# pocketmdm.net
KiCad netlist of a schematic drawn in EAGLE
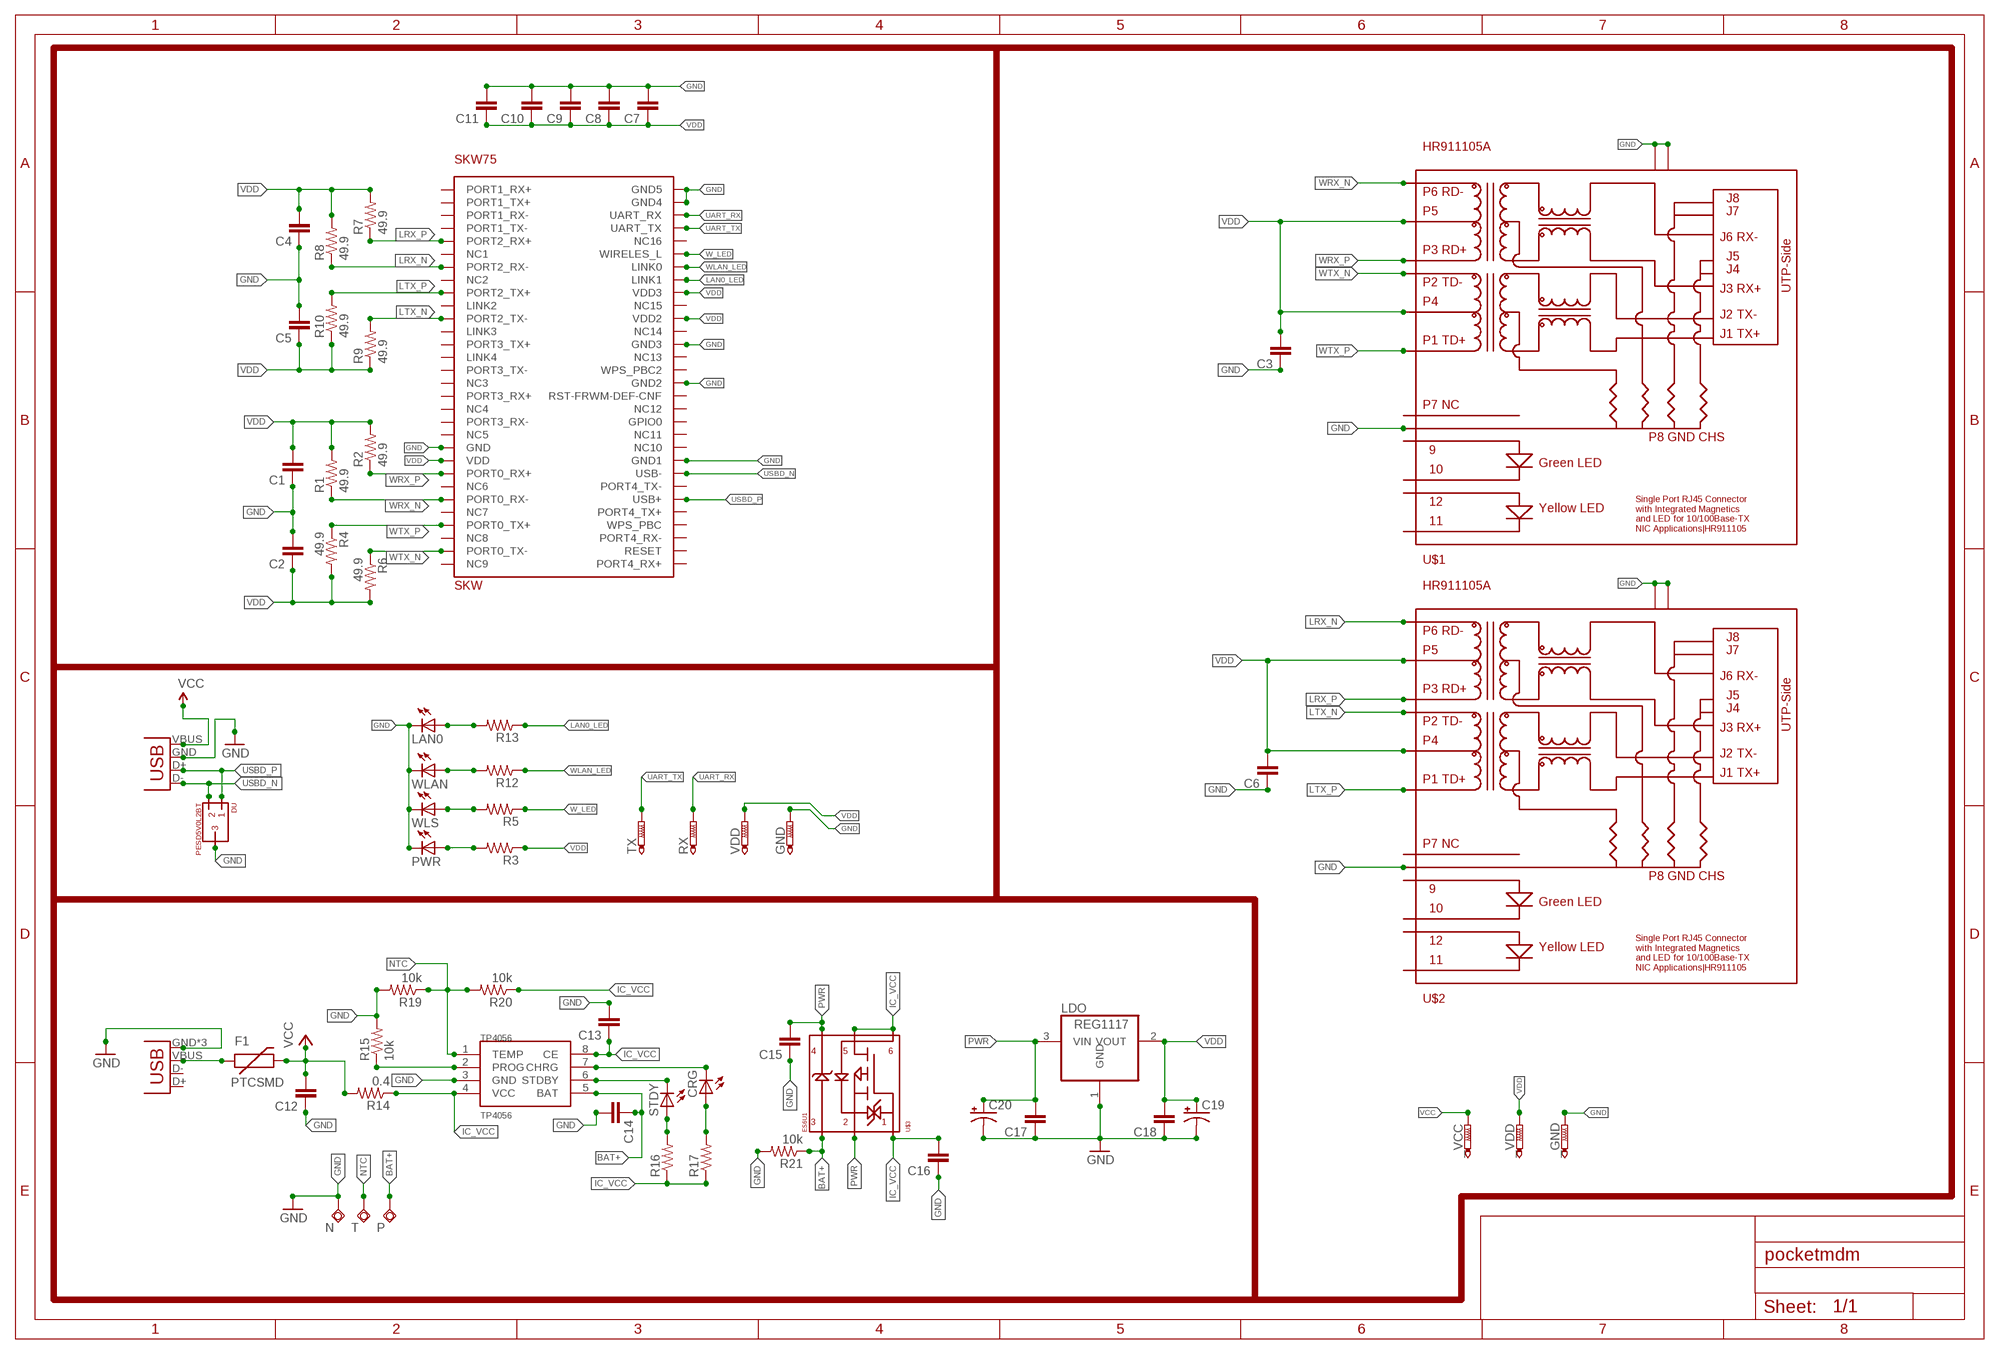
[diagram p0: schematic, sheet 1]

(export (version "E")
  (design (tool "Eeschema 10.0.6"))
  (components
    (comp (ref "C1")
      (value "CAP0402-CAP")
      (footprint "eagle-import:0402-CAP")
      (libsource (lib "eagle-import") (part "CAP0402-CAP"))
    )
    (comp (ref "C2")
      (value "CAP0402-CAP")
      (footprint "eagle-import:0402-CAP")
      (libsource (lib "eagle-import") (part "CAP0402-CAP"))
    )
    (comp (ref "C3")
      (value "CAP0402-CAP")
      (footprint "eagle-import:0402-CAP")
      (libsource (lib "eagle-import") (part "CAP0402-CAP"))
    )
    (comp (ref "C4")
      (value "CAP0402-CAP")
      (footprint "eagle-import:0402-CAP")
      (libsource (lib "eagle-import") (part "CAP0402-CAP"))
    )
    (comp (ref "C5")
      (value "CAP0402-CAP")
      (footprint "eagle-import:0402-CAP")
      (libsource (lib "eagle-import") (part "CAP0402-CAP"))
    )
    (comp (ref "C6")
      (value "CAP0402-CAP")
      (footprint "eagle-import:0402-CAP")
      (libsource (lib "eagle-import") (part "CAP0402-CAP"))
    )
    (comp (ref "C7")
      (value "CAP0402-CAP")
      (footprint "eagle-import:0402-CAP")
      (libsource (lib "eagle-import") (part "CAP0402-CAP"))
    )
    (comp (ref "C8")
      (value "CAP0402-CAP")
      (footprint "eagle-import:0402-CAP")
      (libsource (lib "eagle-import") (part "CAP0402-CAP"))
    )
    (comp (ref "C9")
      (value "CAP0402-CAP")
      (footprint "eagle-import:0402-CAP")
      (libsource (lib "eagle-import") (part "CAP0402-CAP"))
    )
    (comp (ref "C10")
      (value "CAP0402-CAP")
      (footprint "eagle-import:0402-CAP")
      (libsource (lib "eagle-import") (part "CAP0402-CAP"))
    )
    (comp (ref "C11")
      (value "CAP0402-CAP")
      (footprint "eagle-import:0402-CAP")
      (libsource (lib "eagle-import") (part "CAP0402-CAP"))
    )
    (comp (ref "C12")
      (value "CAP0402-CAP")
      (footprint "eagle-import:0402-CAP")
      (libsource (lib "eagle-import") (part "CAP0402-CAP"))
    )
    (comp (ref "C13")
      (value "CAP0402-CAP")
      (footprint "eagle-import:0402-CAP")
      (libsource (lib "eagle-import") (part "CAP0402-CAP"))
    )
    (comp (ref "C14")
      (value "CAP0402-CAP")
      (footprint "eagle-import:0402-CAP")
      (libsource (lib "eagle-import") (part "CAP0402-CAP"))
    )
    (comp (ref "C15")
      (value "CAP0402-CAP")
      (footprint "eagle-import:0402-CAP")
      (libsource (lib "eagle-import") (part "CAP0402-CAP"))
    )
    (comp (ref "C16")
      (value "CAP0402-CAP")
      (footprint "eagle-import:0402-CAP")
      (libsource (lib "eagle-import") (part "CAP0402-CAP"))
    )
    (comp (ref "C17")
      (value "CAP0402-CAP")
      (footprint "eagle-import:0402-CAP")
      (libsource (lib "eagle-import") (part "CAP0402-CAP"))
    )
    (comp (ref "C18")
      (value "CAP0402-CAP")
      (footprint "eagle-import:0402-CAP")
      (libsource (lib "eagle-import") (part "CAP0402-CAP"))
    )
    (comp (ref "C19")
      (value "CAP_POLPTH1")
      (footprint "eagle-import:CPOL-RADIAL-100UF-25V")
      (libsource (lib "eagle-import") (part "CAP_POLPTH1"))
    )
    (comp (ref "C20")
      (value "CAP_POLPTH1")
      (footprint "eagle-import:CPOL-RADIAL-100UF-25V")
      (libsource (lib "eagle-import") (part "CAP_POLPTH1"))
    )
    (comp (ref "CRG")
      (value "LEDCHIPLED_0603")
      (footprint "eagle-import:CHIPLED_0603")
      (libsource (lib "eagle-import") (part "LEDCHIPLED_0603"))
    )
    (comp (ref "DU")
      (value "PESD5V0L2BT")
      (footprint "eagle-import:SOT23")
      (libsource (lib "eagle-import") (part "PESD5V0L2BT"))
    )
    (comp (ref "F1")
      (value "PTCSMD")
      (footprint "eagle-import:PTC-1206")
      (libsource (lib "eagle-import") (part "PTCSMD"))
    )
    (comp (ref "GND")
      (value "PTR1B1,27")
      (footprint "eagle-import:B1,27")
      (libsource (lib "eagle-import") (part "PTR1B1,27"))
    )
    (comp (ref "LAN0")
      (value "LEDCHIPLED_0603")
      (footprint "eagle-import:CHIPLED_0603")
      (libsource (lib "eagle-import") (part "LEDCHIPLED_0603"))
    )
    (comp (ref "LDO")
      (value "REG1117")
      (footprint "eagle-import:SOT223")
      (libsource (lib "eagle-import") (part "REG1117"))
    )
    (comp (ref "N")
      (value "TPSQTP20SQ")
      (footprint "eagle-import:TP20SQ")
      (libsource (lib "eagle-import") (part "TPSQTP20SQ"))
    )
    (comp (ref "P")
      (value "TPSQTP20SQ")
      (footprint "eagle-import:TP20SQ")
      (libsource (lib "eagle-import") (part "TPSQTP20SQ"))
    )
    (comp (ref "PWR")
      (value "LEDCHIPLED_0603")
      (footprint "eagle-import:CHIPLED_0603")
      (libsource (lib "eagle-import") (part "LEDCHIPLED_0603"))
    )
    (comp (ref "R1")
      (value "49.9")
      (footprint "eagle-import:0402-RES")
      (libsource (lib "eagle-import") (part "RESISTOR0402-RES"))
    )
    (comp (ref "R2")
      (value "49.9")
      (footprint "eagle-import:0402-RES")
      (libsource (lib "eagle-import") (part "RESISTOR0402-RES"))
    )
    (comp (ref "R3")
      (value "RESISTOR0402-RES")
      (footprint "eagle-import:0402-RES")
      (libsource (lib "eagle-import") (part "RESISTOR0402-RES"))
    )
    (comp (ref "R4")
      (value "49.9")
      (footprint "eagle-import:0402-RES")
      (libsource (lib "eagle-import") (part "RESISTOR0402-RES"))
    )
    (comp (ref "R5")
      (value "RESISTOR0402-RES")
      (footprint "eagle-import:0402-RES")
      (libsource (lib "eagle-import") (part "RESISTOR0402-RES"))
    )
    (comp (ref "R6")
      (value "49.9")
      (footprint "eagle-import:0402-RES")
      (libsource (lib "eagle-import") (part "RESISTOR0402-RES"))
    )
    (comp (ref "R7")
      (value "49.9")
      (footprint "eagle-import:0402-RES")
      (libsource (lib "eagle-import") (part "RESISTOR0402-RES"))
    )
    (comp (ref "R8")
      (value "49.9")
      (footprint "eagle-import:0402-RES")
      (libsource (lib "eagle-import") (part "RESISTOR0402-RES"))
    )
    (comp (ref "R9")
      (value "49.9")
      (footprint "eagle-import:0402-RES")
      (libsource (lib "eagle-import") (part "RESISTOR0402-RES"))
    )
    (comp (ref "R10")
      (value "49.9")
      (footprint "eagle-import:0402-RES")
      (libsource (lib "eagle-import") (part "RESISTOR0402-RES"))
    )
    (comp (ref "R12")
      (value "RESISTOR0402-RES")
      (footprint "eagle-import:0402-RES")
      (libsource (lib "eagle-import") (part "RESISTOR0402-RES"))
    )
    (comp (ref "R13")
      (value "RESISTOR0402-RES")
      (footprint "eagle-import:0402-RES")
      (libsource (lib "eagle-import") (part "RESISTOR0402-RES"))
    )
    (comp (ref "R14")
      (value "0.4")
      (footprint "eagle-import:0402-RES")
      (libsource (lib "eagle-import") (part "RESISTOR0402-RES"))
    )
    (comp (ref "R15")
      (value "10k")
      (footprint "eagle-import:0402-RES")
      (libsource (lib "eagle-import") (part "RESISTOR0402-RES"))
    )
    (comp (ref "R16")
      (value "RESISTOR0402-RES")
      (footprint "eagle-import:0402-RES")
      (libsource (lib "eagle-import") (part "RESISTOR0402-RES"))
    )
    (comp (ref "R17")
      (value "RESISTOR0402-RES")
      (footprint "eagle-import:0402-RES")
      (libsource (lib "eagle-import") (part "RESISTOR0402-RES"))
    )
    (comp (ref "R19")
      (value "10k")
      (footprint "eagle-import:0402-RES")
      (libsource (lib "eagle-import") (part "RESISTOR0402-RES"))
    )
    (comp (ref "R20")
      (value "10k")
      (footprint "eagle-import:0402-RES")
      (libsource (lib "eagle-import") (part "RESISTOR0402-RES"))
    )
    (comp (ref "R21")
      (value "10k")
      (footprint "eagle-import:0402-RES")
      (libsource (lib "eagle-import") (part "RESISTOR0402-RES"))
    )
    (comp (ref "RX")
      (value "PTR1B1,27")
      (footprint "eagle-import:B1,27")
      (libsource (lib "eagle-import") (part "PTR1B1,27"))
    )
    (comp (ref "SKW")
      (value "SKW75")
      (footprint "eagle-import:CON-60-127MMPTH")
      (libsource (lib "eagle-import") (part "SKW75"))
    )
    (comp (ref "STDY")
      (value "LEDCHIPLED_0603")
      (footprint "eagle-import:CHIPLED_0603")
      (libsource (lib "eagle-import") (part "LEDCHIPLED_0603"))
    )
    (comp (ref "T")
      (value "TPSQTP20SQ")
      (footprint "eagle-import:TP20SQ")
      (libsource (lib "eagle-import") (part "TPSQTP20SQ"))
    )
    (comp (ref "TP4056")
      (value "TP4056")
      (footprint "eagle-import:SOP-8")
      (libsource (lib "eagle-import") (part "TP4056"))
    )
    (comp (ref "TX")
      (value "PTR1B1,27")
      (footprint "eagle-import:B1,27")
      (libsource (lib "eagle-import") (part "PTR1B1,27"))
    )
    (comp (ref "U$1")
      (value "HR911105A")
      (footprint "eagle-import:HR911105A")
      (libsource (lib "eagle-import") (part "HR911105A"))
    )
    (comp (ref "U$2")
      (value "HR911105A")
      (footprint "eagle-import:HR911105A")
      (libsource (lib "eagle-import") (part "HR911105A"))
    )
    (comp (ref "U$3")
      (value "ES6U1")
      (footprint "eagle-import:WEMT6")
      (libsource (lib "eagle-import") (part "ES6U1"))
    )
    (comp (ref "USBA")
      (value "USB-A-H")
      (footprint "eagle-import:USB-A-H")
      (libsource (lib "eagle-import") (part "USB-A-H"))
    )
    (comp (ref "USBM")
      (value "USB-MICROB")
      (footprint "eagle-import:USB-MICROB")
      (libsource (lib "eagle-import") (part "USB-MICROB"))
    )
    (comp (ref "VDD")
      (value "PTR1B1,27")
      (footprint "eagle-import:B1,27")
      (libsource (lib "eagle-import") (part "PTR1B1,27"))
    )
    (comp (ref "WLAN")
      (value "LEDCHIPLED_0603")
      (footprint "eagle-import:CHIPLED_0603")
      (libsource (lib "eagle-import") (part "LEDCHIPLED_0603"))
    )
    (comp (ref "WLS")
      (value "LEDCHIPLED_0603")
      (footprint "eagle-import:CHIPLED_0603")
      (libsource (lib "eagle-import") (part "LEDCHIPLED_0603"))
    )
    (comp (ref "_GND")
      (value "PTR1B1,27")
      (footprint "eagle-import:B1,27")
      (libsource (lib "eagle-import") (part "PTR1B1,27"))
    )
    (comp (ref "_VCC")
      (value "PTR1B1,27")
      (footprint "eagle-import:B1,27")
      (libsource (lib "eagle-import") (part "PTR1B1,27"))
    )
    (comp (ref "_VDD")
      (value "PTR1B1,27")
      (footprint "eagle-import:B1,27")
      (libsource (lib "eagle-import") (part "PTR1B1,27"))
    )
  )
  (nets
    (net (code "1") (name "BAT+") (class "Default")
      (node (ref "C14") (pin "1") (pinfunction "1_1") (pintype "passive"))
      (node (ref "P") (pin "TP") (pinfunction "TP_TP") (pintype "input"))
      (node (ref "R21") (pin "1") (pinfunction "1_1") (pintype "passive"))
      (node (ref "TP4056") (pin "5") (pinfunction "BAT_5") (pintype "bidirectional"))
      (node (ref "U$3") (pin "P$3") (pinfunction "P$3_P$3") (pintype "bidirectional"))
    )
    (net (code "2") (name "GND") (class "Default")
      (node (ref "C1") (pin "1") (pinfunction "1_1") (pintype "passive"))
      (node (ref "C10") (pin "2") (pinfunction "2_2") (pintype "passive"))
      (node (ref "C11") (pin "2") (pinfunction "2_2") (pintype "passive"))
      (node (ref "C12") (pin "1") (pinfunction "1_1") (pintype "passive"))
      (node (ref "C13") (pin "2") (pinfunction "2_2") (pintype "passive"))
      (node (ref "C14") (pin "2") (pinfunction "2_2") (pintype "passive"))
      (node (ref "C15") (pin "1") (pinfunction "1_1") (pintype "passive"))
      (node (ref "C16") (pin "1") (pinfunction "1_1") (pintype "passive"))
      (node (ref "C17") (pin "1") (pinfunction "1_1") (pintype "passive"))
      (node (ref "C18") (pin "1") (pinfunction "1_1") (pintype "passive"))
      (node (ref "C19") (pin "2") (pinfunction "-_2") (pintype "passive"))
      (node (ref "C2") (pin "2") (pinfunction "2_2") (pintype "passive"))
      (node (ref "C20") (pin "2") (pinfunction "-_2") (pintype "passive"))
      (node (ref "C3") (pin "1") (pinfunction "1_1") (pintype "passive"))
      (node (ref "C4") (pin "1") (pinfunction "1_1") (pintype "passive"))
      (node (ref "C5") (pin "2") (pinfunction "2_2") (pintype "passive"))
      (node (ref "C6") (pin "1") (pinfunction "1_1") (pintype "passive"))
      (node (ref "C7") (pin "2") (pinfunction "2_2") (pintype "passive"))
      (node (ref "C8") (pin "2") (pinfunction "2_2") (pintype "passive"))
      (node (ref "C9") (pin "2") (pinfunction "2_2") (pintype "passive"))
      (node (ref "DU") (pin "3") (pinfunction "P$3_3") (pintype "bidirectional"))
      (node (ref "GND") (pin "TP") (pinfunction "TP_TP") (pintype "input"))
      (node (ref "LAN0") (pin "C") (pinfunction "C_C") (pintype "passive"))
      (node (ref "LDO") (pin "1") (pinfunction "GND_1") (pintype "power_in"))
      (node (ref "N") (pin "TP") (pinfunction "TP_TP") (pintype "input"))
      (node (ref "PWR") (pin "C") (pinfunction "C_C") (pintype "passive"))
      (node (ref "R15") (pin "2") (pinfunction "2_2") (pintype "passive"))
      (node (ref "R19") (pin "2") (pinfunction "2_2") (pintype "passive"))
      (node (ref "R21") (pin "2") (pinfunction "2_2") (pintype "passive"))
      (node (ref "SKW") (pin "P$21") (pinfunction "GND_P$21") (pintype "bidirectional"))
      (node (ref "SKW") (pin "P$39") (pinfunction "GND1_P$39") (pintype "bidirectional"))
      (node (ref "SKW") (pin "P$45") (pinfunction "GND2_P$45") (pintype "bidirectional"))
      (node (ref "SKW") (pin "P$48") (pinfunction "GND3_P$48") (pintype "bidirectional"))
      (node (ref "SKW") (pin "P$59") (pinfunction "GND4_P$59") (pintype "bidirectional"))
      (node (ref "SKW") (pin "P$60") (pinfunction "GND5_P$60") (pintype "bidirectional"))
      (node (ref "TP4056") (pin "3") (pinfunction "GND_3") (pintype "bidirectional"))
      (node (ref "U$1") (pin "P$13") (pinfunction "P$13_P$13") (pintype "bidirectional"))
      (node (ref "U$1") (pin "P$14") (pinfunction "P$14_P$14") (pintype "bidirectional"))
      (node (ref "U$1") (pin "P$8") (pinfunction "P$8_P$8") (pintype "bidirectional"))
      (node (ref "U$2") (pin "P$13") (pinfunction "P$13_P$13") (pintype "bidirectional"))
      (node (ref "U$2") (pin "P$14") (pinfunction "P$14_P$14") (pintype "bidirectional"))
      (node (ref "U$2") (pin "P$8") (pinfunction "P$8_P$8") (pintype "bidirectional"))
      (node (ref "USBA") (pin "GND") (pinfunction "VBUS_GND") (pintype "bidirectional"))
      (node (ref "USBM") (pin "GND") (pinfunction "GND_GND") (pintype "bidirectional"))
      (node (ref "USBM") (pin "MT1") (pinfunction "GND_MT1") (pintype "bidirectional"))
      (node (ref "USBM") (pin "MT2") (pinfunction "GND_MT2") (pintype "bidirectional"))
      (node (ref "WLAN") (pin "C") (pinfunction "C_C") (pintype "passive"))
      (node (ref "WLS") (pin "C") (pinfunction "C_C") (pintype "passive"))
      (node (ref "_GND") (pin "TP") (pinfunction "TP_TP") (pintype "input"))
    )
    (net (code "3") (name "IC_VCC") (class "Default")
      (node (ref "C13") (pin "1") (pinfunction "1_1") (pintype "passive"))
      (node (ref "C16") (pin "2") (pinfunction "2_2") (pintype "passive"))
      (node (ref "R14") (pin "1") (pinfunction "1_1") (pintype "passive"))
      (node (ref "R16") (pin "1") (pinfunction "1_1") (pintype "passive"))
      (node (ref "R17") (pin "1") (pinfunction "1_1") (pintype "passive"))
      (node (ref "R20") (pin "1") (pinfunction "1_1") (pintype "passive"))
      (node (ref "TP4056") (pin "4") (pinfunction "VCC_4") (pintype "bidirectional"))
      (node (ref "TP4056") (pin "8") (pinfunction "CE_8") (pintype "bidirectional"))
      (node (ref "U$3") (pin "P$1") (pinfunction "P$1_P$1") (pintype "bidirectional"))
      (node (ref "U$3") (pin "P$5") (pinfunction "P$5_P$5") (pintype "bidirectional"))
      (node (ref "U$3") (pin "P$6") (pinfunction "P$6_P$6") (pintype "bidirectional"))
    )
    (net (code "4") (name "LAN0_LED") (class "Default")
      (node (ref "R13") (pin "1") (pinfunction "1_1") (pintype "passive"))
      (node (ref "SKW") (pin "P$53") (pinfunction "LINK1_P$53") (pintype "bidirectional"))
    )
    (net (code "5") (name "LRX_N") (class "Default")
      (node (ref "R8") (pin "1") (pinfunction "1_1") (pintype "passive"))
      (node (ref "SKW") (pin "P$7") (pinfunction "PORT2_RX-_P$7") (pintype "bidirectional"))
      (node (ref "U$2") (pin "P$6") (pinfunction "P$6_P$6") (pintype "bidirectional"))
    )
    (net (code "6") (name "LRX_P") (class "Default")
      (node (ref "R7") (pin "1") (pinfunction "1_1") (pintype "passive"))
      (node (ref "SKW") (pin "P$5") (pinfunction "PORT2_RX+_P$5") (pintype "bidirectional"))
      (node (ref "U$2") (pin "P$3") (pinfunction "P$3_P$3") (pintype "bidirectional"))
    )
    (net (code "7") (name "LTX_N") (class "Default")
      (node (ref "R9") (pin "2") (pinfunction "2_2") (pintype "passive"))
      (node (ref "SKW") (pin "P$11") (pinfunction "PORT2_TX-_P$11") (pintype "bidirectional"))
      (node (ref "U$2") (pin "P$2") (pinfunction "P$2_P$2") (pintype "bidirectional"))
    )
    (net (code "8") (name "LTX_P") (class "Default")
      (node (ref "R10") (pin "2") (pinfunction "2_2") (pintype "passive"))
      (node (ref "SKW") (pin "P$9") (pinfunction "PORT2_TX+_P$9") (pintype "bidirectional"))
      (node (ref "U$2") (pin "P$1") (pinfunction "P$1_P$1") (pintype "bidirectional"))
    )
    (net (code "9") (name "NTC") (class "Default")
      (node (ref "R19") (pin "1") (pinfunction "1_1") (pintype "passive"))
      (node (ref "R20") (pin "2") (pinfunction "2_2") (pintype "passive"))
      (node (ref "T") (pin "TP") (pinfunction "TP_TP") (pintype "input"))
      (node (ref "TP4056") (pin "1") (pinfunction "TEMP_1") (pintype "bidirectional"))
    )
    (net (code "10") (name "Net-(CRG-PadA)") (class "Default")
      (node (ref "CRG") (pin "A") (pinfunction "A_A") (pintype "passive"))
      (node (ref "R17") (pin "2") (pinfunction "2_2") (pintype "passive"))
    )
    (net (code "11") (name "Net-(F1-Pad1)") (class "Default")
      (node (ref "F1") (pin "1") (pinfunction "1_1") (pintype "bidirectional"))
      (node (ref "USBM") (pin "VBUS") (pinfunction "VBUS_VBUS") (pintype "bidirectional"))
    )
    (net (code "12") (name "Net-(LAN0-PadA)") (class "Default")
      (node (ref "LAN0") (pin "A") (pinfunction "A_A") (pintype "passive"))
      (node (ref "R13") (pin "2") (pinfunction "2_2") (pintype "passive"))
    )
    (net (code "13") (name "Net-(PWR-PadA)") (class "Default")
      (node (ref "PWR") (pin "A") (pinfunction "A_A") (pintype "passive"))
      (node (ref "R3") (pin "2") (pinfunction "2_2") (pintype "passive"))
    )
    (net (code "14") (name "Net-(R5-Pad2)") (class "Default")
      (node (ref "R5") (pin "2") (pinfunction "2_2") (pintype "passive"))
      (node (ref "WLS") (pin "A") (pinfunction "A_A") (pintype "passive"))
    )
    (net (code "15") (name "Net-(R12-Pad2)") (class "Default")
      (node (ref "R12") (pin "2") (pinfunction "2_2") (pintype "passive"))
      (node (ref "WLAN") (pin "A") (pinfunction "A_A") (pintype "passive"))
    )
    (net (code "16") (name "Net-(R16-Pad2)") (class "Default")
      (node (ref "R16") (pin "2") (pinfunction "2_2") (pintype "passive"))
      (node (ref "STDY") (pin "A") (pinfunction "A_A") (pintype "passive"))
    )
    (net (code "17") (name "Net-(TP4056-CHRG)") (class "Default")
      (node (ref "CRG") (pin "C") (pinfunction "C_C") (pintype "passive"))
      (node (ref "TP4056") (pin "7") (pinfunction "CHRG_7") (pintype "bidirectional"))
    )
    (net (code "18") (name "Net-(TP4056-PROG)") (class "Default")
      (node (ref "R15") (pin "1") (pinfunction "1_1") (pintype "passive"))
      (node (ref "TP4056") (pin "2") (pinfunction "PROG_2") (pintype "bidirectional"))
    )
    (net (code "19") (name "Net-(TP4056-STDBY)") (class "Default")
      (node (ref "STDY") (pin "C") (pinfunction "C_C") (pintype "passive"))
      (node (ref "TP4056") (pin "6") (pinfunction "STDBY_6") (pintype "bidirectional"))
    )
    (net (code "20") (name "PWR") (class "Default")
      (node (ref "C15") (pin "2") (pinfunction "2_2") (pintype "passive"))
      (node (ref "C17") (pin "2") (pinfunction "2_2") (pintype "passive"))
      (node (ref "C20") (pin "1") (pinfunction "+_1") (pintype "passive"))
      (node (ref "LDO") (pin "3") (pinfunction "VIN_3") (pintype "input"))
      (node (ref "U$3") (pin "P$2") (pinfunction "P$2_P$2") (pintype "bidirectional"))
      (node (ref "U$3") (pin "P$4") (pinfunction "P$4_P$4") (pintype "bidirectional"))
    )
    (net (code "21") (name "UART_RX") (class "Default")
      (node (ref "RX") (pin "TP") (pinfunction "TP_TP") (pintype "input"))
      (node (ref "SKW") (pin "P$58") (pinfunction "UART_RX_P$58") (pintype "bidirectional"))
    )
    (net (code "22") (name "UART_TX") (class "Default")
      (node (ref "SKW") (pin "P$57") (pinfunction "UART_TX_P$57") (pintype "bidirectional"))
      (node (ref "TX") (pin "TP") (pinfunction "TP_TP") (pintype "input"))
    )
    (net (code "23") (name "USBD_N") (class "Default")
      (node (ref "DU") (pin "2") (pinfunction "P$2_2") (pintype "bidirectional"))
      (node (ref "SKW") (pin "P$38") (pinfunction "USB-_P$38") (pintype "bidirectional"))
      (node (ref "USBA") (pin "D-") (pinfunction "D+_D-") (pintype "bidirectional"))
    )
    (net (code "24") (name "USBD_P") (class "Default")
      (node (ref "DU") (pin "1") (pinfunction "P$1_1") (pintype "bidirectional"))
      (node (ref "SKW") (pin "P$36") (pinfunction "USB+_P$36") (pintype "bidirectional"))
      (node (ref "USBA") (pin "D+") (pinfunction "D-_D+") (pintype "bidirectional"))
    )
    (net (code "25") (name "VCC") (class "Default")
      (node (ref "C12") (pin "2") (pinfunction "2_2") (pintype "passive"))
      (node (ref "F1") (pin "2") (pinfunction "2_2") (pintype "bidirectional"))
      (node (ref "R14") (pin "2") (pinfunction "2_2") (pintype "passive"))
      (node (ref "USBA") (pin "VBUS") (pinfunction "GND_VBUS") (pintype "bidirectional"))
      (node (ref "_VCC") (pin "TP") (pinfunction "TP_TP") (pintype "input"))
    )
    (net (code "26") (name "VDD") (class "Default")
      (node (ref "C1") (pin "2") (pinfunction "2_2") (pintype "passive"))
      (node (ref "C10") (pin "1") (pinfunction "1_1") (pintype "passive"))
      (node (ref "C11") (pin "1") (pinfunction "1_1") (pintype "passive"))
      (node (ref "C18") (pin "2") (pinfunction "2_2") (pintype "passive"))
      (node (ref "C19") (pin "1") (pinfunction "+_1") (pintype "passive"))
      (node (ref "C2") (pin "1") (pinfunction "1_1") (pintype "passive"))
      (node (ref "C3") (pin "2") (pinfunction "2_2") (pintype "passive"))
      (node (ref "C4") (pin "2") (pinfunction "2_2") (pintype "passive"))
      (node (ref "C5") (pin "1") (pinfunction "1_1") (pintype "passive"))
      (node (ref "C6") (pin "2") (pinfunction "2_2") (pintype "passive"))
      (node (ref "C7") (pin "1") (pinfunction "1_1") (pintype "passive"))
      (node (ref "C8") (pin "1") (pinfunction "1_1") (pintype "passive"))
      (node (ref "C9") (pin "1") (pinfunction "1_1") (pintype "passive"))
      (node (ref "LDO") (pin "2") (pinfunction "VOUT_2") (pintype "output"))
      (node (ref "R1") (pin "2") (pinfunction "2_2") (pintype "passive"))
      (node (ref "R10") (pin "1") (pinfunction "1_1") (pintype "passive"))
      (node (ref "R2") (pin "2") (pinfunction "2_2") (pintype "passive"))
      (node (ref "R3") (pin "1") (pinfunction "1_1") (pintype "passive"))
      (node (ref "R4") (pin "2") (pinfunction "2_2") (pintype "passive"))
      (node (ref "R6") (pin "2") (pinfunction "2_2") (pintype "passive"))
      (node (ref "R7") (pin "2") (pinfunction "2_2") (pintype "passive"))
      (node (ref "R8") (pin "2") (pinfunction "2_2") (pintype "passive"))
      (node (ref "R9") (pin "1") (pinfunction "1_1") (pintype "passive"))
      (node (ref "SKW") (pin "P$22") (pinfunction "VDD_P$22") (pintype "bidirectional"))
      (node (ref "SKW") (pin "P$50") (pinfunction "VDD2_P$50") (pintype "bidirectional"))
      (node (ref "SKW") (pin "P$52") (pinfunction "VDD3_P$52") (pintype "bidirectional"))
      (node (ref "U$1") (pin "P$4") (pinfunction "P$4_P$4") (pintype "bidirectional"))
      (node (ref "U$1") (pin "P$5") (pinfunction "P$5_P$5") (pintype "bidirectional"))
      (node (ref "U$2") (pin "P$4") (pinfunction "P$4_P$4") (pintype "bidirectional"))
      (node (ref "U$2") (pin "P$5") (pinfunction "P$5_P$5") (pintype "bidirectional"))
      (node (ref "VDD") (pin "TP") (pinfunction "TP_TP") (pintype "input"))
      (node (ref "_VDD") (pin "TP") (pinfunction "TP_TP") (pintype "input"))
    )
    (net (code "27") (name "WLAN_LED") (class "Default")
      (node (ref "R12") (pin "1") (pinfunction "1_1") (pintype "passive"))
      (node (ref "SKW") (pin "P$54") (pinfunction "LINK0_P$54") (pintype "bidirectional"))
    )
    (net (code "28") (name "WRX_N") (class "Default")
      (node (ref "R1") (pin "1") (pinfunction "1_1") (pintype "passive"))
      (node (ref "SKW") (pin "P$25") (pinfunction "PORT0_RX-_P$25") (pintype "bidirectional"))
      (node (ref "U$1") (pin "P$6") (pinfunction "P$6_P$6") (pintype "bidirectional"))
    )
    (net (code "29") (name "WRX_P") (class "Default")
      (node (ref "R2") (pin "1") (pinfunction "1_1") (pintype "passive"))
      (node (ref "SKW") (pin "P$23") (pinfunction "PORT0_RX+_P$23") (pintype "bidirectional"))
      (node (ref "U$1") (pin "P$3") (pinfunction "P$3_P$3") (pintype "bidirectional"))
    )
    (net (code "30") (name "WTX_N") (class "Default")
      (node (ref "R6") (pin "1") (pinfunction "1_1") (pintype "passive"))
      (node (ref "SKW") (pin "P$29") (pinfunction "PORT0_TX-_P$29") (pintype "bidirectional"))
      (node (ref "U$1") (pin "P$2") (pinfunction "P$2_P$2") (pintype "bidirectional"))
    )
    (net (code "31") (name "WTX_P") (class "Default")
      (node (ref "R4") (pin "1") (pinfunction "1_1") (pintype "passive"))
      (node (ref "SKW") (pin "P$27") (pinfunction "PORT0_TX+_P$27") (pintype "bidirectional"))
      (node (ref "U$1") (pin "P$1") (pinfunction "P$1_P$1") (pintype "bidirectional"))
    )
    (net (code "32") (name "W_LED") (class "Default")
      (node (ref "R5") (pin "1") (pinfunction "1_1") (pintype "passive"))
      (node (ref "SKW") (pin "P$55") (pinfunction "WIRELES_L_P$55") (pintype "bidirectional"))
    )
    (net (code "33") (name "unconnected-(SKW-GPIO0-PadP$42)") (class "Default")
      (node (ref "SKW") (pin "P$42") (pinfunction "GPIO0_P$42") (pintype "bidirectional"))
    )
    (net (code "34") (name "unconnected-(SKW-LINK2-PadP$10)") (class "Default")
      (node (ref "SKW") (pin "P$10") (pinfunction "LINK2_P$10") (pintype "bidirectional"))
    )
    (net (code "35") (name "unconnected-(SKW-LINK3-PadP$12)") (class "Default")
      (node (ref "SKW") (pin "P$12") (pinfunction "LINK3_P$12") (pintype "bidirectional"))
    )
    (net (code "36") (name "unconnected-(SKW-LINK4-PadP$14)") (class "Default")
      (node (ref "SKW") (pin "P$14") (pinfunction "LINK4_P$14") (pintype "bidirectional"))
    )
    (net (code "37") (name "unconnected-(SKW-NC1-PadP$6)") (class "Default")
      (node (ref "SKW") (pin "P$6") (pinfunction "NC1_P$6") (pintype "bidirectional"))
    )
    (net (code "38") (name "unconnected-(SKW-NC2-PadP$8)") (class "Default")
      (node (ref "SKW") (pin "P$8") (pinfunction "NC2_P$8") (pintype "bidirectional"))
    )
    (net (code "39") (name "unconnected-(SKW-NC3-PadP$16)") (class "Default")
      (node (ref "SKW") (pin "P$16") (pinfunction "NC3_P$16") (pintype "bidirectional"))
    )
    (net (code "40") (name "unconnected-(SKW-NC4-PadP$18)") (class "Default")
      (node (ref "SKW") (pin "P$18") (pinfunction "NC4_P$18") (pintype "bidirectional"))
    )
    (net (code "41") (name "unconnected-(SKW-NC5-PadP$20)") (class "Default")
      (node (ref "SKW") (pin "P$20") (pinfunction "NC5_P$20") (pintype "bidirectional"))
    )
    (net (code "42") (name "unconnected-(SKW-NC6-PadP$24)") (class "Default")
      (node (ref "SKW") (pin "P$24") (pinfunction "NC6_P$24") (pintype "bidirectional"))
    )
    (net (code "43") (name "unconnected-(SKW-NC7-PadP$26)") (class "Default")
      (node (ref "SKW") (pin "P$26") (pinfunction "NC7_P$26") (pintype "bidirectional"))
    )
    (net (code "44") (name "unconnected-(SKW-NC8-PadP$28)") (class "Default")
      (node (ref "SKW") (pin "P$28") (pinfunction "NC8_P$28") (pintype "bidirectional"))
    )
    (net (code "45") (name "unconnected-(SKW-NC9-PadP$30)") (class "Default")
      (node (ref "SKW") (pin "P$30") (pinfunction "NC9_P$30") (pintype "bidirectional"))
    )
    (net (code "46") (name "unconnected-(SKW-NC10-PadP$40)") (class "Default")
      (node (ref "SKW") (pin "P$40") (pinfunction "NC10_P$40") (pintype "bidirectional"))
    )
    (net (code "47") (name "unconnected-(SKW-NC11-PadP$41)") (class "Default")
      (node (ref "SKW") (pin "P$41") (pinfunction "NC11_P$41") (pintype "bidirectional"))
    )
    (net (code "48") (name "unconnected-(SKW-NC12-PadP$43)") (class "Default")
      (node (ref "SKW") (pin "P$43") (pinfunction "NC12_P$43") (pintype "bidirectional"))
    )
    (net (code "49") (name "unconnected-(SKW-NC13-PadP$47)") (class "Default")
      (node (ref "SKW") (pin "P$47") (pinfunction "NC13_P$47") (pintype "bidirectional"))
    )
    (net (code "50") (name "unconnected-(SKW-NC14-PadP$49)") (class "Default")
      (node (ref "SKW") (pin "P$49") (pinfunction "NC14_P$49") (pintype "bidirectional"))
    )
    (net (code "51") (name "unconnected-(SKW-NC15-PadP$51)") (class "Default")
      (node (ref "SKW") (pin "P$51") (pinfunction "NC15_P$51") (pintype "bidirectional"))
    )
    (net (code "52") (name "unconnected-(SKW-NC16-PadP$56)") (class "Default")
      (node (ref "SKW") (pin "P$56") (pinfunction "NC16_P$56") (pintype "bidirectional"))
    )
    (net (code "53") (name "unconnected-(SKW-PORT1_RX+-PadP$1)") (class "Default")
      (node (ref "SKW") (pin "P$1") (pinfunction "PORT1_RX+_P$1") (pintype "bidirectional"))
    )
    (net (code "54") (name "unconnected-(SKW-PORT1_RX--PadP$3)") (class "Default")
      (node (ref "SKW") (pin "P$3") (pinfunction "PORT1_RX-_P$3") (pintype "bidirectional"))
    )
    (net (code "55") (name "unconnected-(SKW-PORT1_TX+-PadP$2)") (class "Default")
      (node (ref "SKW") (pin "P$2") (pinfunction "PORT1_TX+_P$2") (pintype "bidirectional"))
    )
    (net (code "56") (name "unconnected-(SKW-PORT1_TX--PadP$4)") (class "Default")
      (node (ref "SKW") (pin "P$4") (pinfunction "PORT1_TX-_P$4") (pintype "bidirectional"))
    )
    (net (code "57") (name "unconnected-(SKW-PORT3_RX+-PadP$17)") (class "Default")
      (node (ref "SKW") (pin "P$17") (pinfunction "PORT3_RX+_P$17") (pintype "bidirectional"))
    )
    (net (code "58") (name "unconnected-(SKW-PORT3_RX--PadP$19)") (class "Default")
      (node (ref "SKW") (pin "P$19") (pinfunction "PORT3_RX-_P$19") (pintype "bidirectional"))
    )
    (net (code "59") (name "unconnected-(SKW-PORT3_TX+-PadP$13)") (class "Default")
      (node (ref "SKW") (pin "P$13") (pinfunction "PORT3_TX+_P$13") (pintype "bidirectional"))
    )
    (net (code "60") (name "unconnected-(SKW-PORT3_TX--PadP$15)") (class "Default")
      (node (ref "SKW") (pin "P$15") (pinfunction "PORT3_TX-_P$15") (pintype "bidirectional"))
    )
    (net (code "61") (name "unconnected-(SKW-PORT4_RX+-PadP$31)") (class "Default")
      (node (ref "SKW") (pin "P$31") (pinfunction "PORT4_RX+_P$31") (pintype "bidirectional"))
    )
    (net (code "62") (name "unconnected-(SKW-PORT4_RX--PadP$33)") (class "Default")
      (node (ref "SKW") (pin "P$33") (pinfunction "PORT4_RX-_P$33") (pintype "bidirectional"))
    )
    (net (code "63") (name "unconnected-(SKW-PORT4_TX+-PadP$35)") (class "Default")
      (node (ref "SKW") (pin "P$35") (pinfunction "PORT4_TX+_P$35") (pintype "bidirectional"))
    )
    (net (code "64") (name "unconnected-(SKW-PORT4_TX--PadP$37)") (class "Default")
      (node (ref "SKW") (pin "P$37") (pinfunction "PORT4_TX-_P$37") (pintype "bidirectional"))
    )
    (net (code "65") (name "unconnected-(SKW-RESET-PadP$32)") (class "Default")
      (node (ref "SKW") (pin "P$32") (pinfunction "RESET_P$32") (pintype "bidirectional"))
    )
    (net (code "66") (name "unconnected-(SKW-RST-FRWM-DEF-CNF-PadP$44)") (class "Default")
      (node (ref "SKW") (pin "P$44") (pinfunction "RST-FRWM-DEF-CNF_P$44") (pintype "bidirectional"))
    )
    (net (code "67") (name "unconnected-(SKW-WPS_PBC-PadP$34)") (class "Default")
      (node (ref "SKW") (pin "P$34") (pinfunction "WPS_PBC_P$34") (pintype "bidirectional"))
    )
    (net (code "68") (name "unconnected-(SKW-WPS_PBC2-PadP$46)") (class "Default")
      (node (ref "SKW") (pin "P$46") (pinfunction "WPS_PBC2_P$46") (pintype "bidirectional"))
    )
    (net (code "69") (name "unconnected-(U$1-PadP$7)") (class "Default")
      (node (ref "U$1") (pin "P$7") (pinfunction "P$7_P$7") (pintype "bidirectional"))
    )
    (net (code "70") (name "unconnected-(U$1-PadP$9)") (class "Default")
      (node (ref "U$1") (pin "P$9") (pinfunction "P$9_P$9") (pintype "bidirectional"))
    )
    (net (code "71") (name "unconnected-(U$1-PadP$10)") (class "Default")
      (node (ref "U$1") (pin "P$10") (pinfunction "P$10_P$10") (pintype "bidirectional"))
    )
    (net (code "72") (name "unconnected-(U$1-PadP$11)") (class "Default")
      (node (ref "U$1") (pin "P$11") (pinfunction "P$11_P$11") (pintype "bidirectional"))
    )
    (net (code "73") (name "unconnected-(U$1-PadP$12)") (class "Default")
      (node (ref "U$1") (pin "P$12") (pinfunction "P$12_P$12") (pintype "bidirectional"))
    )
    (net (code "74") (name "unconnected-(U$2-PadP$7)") (class "Default")
      (node (ref "U$2") (pin "P$7") (pinfunction "P$7_P$7") (pintype "bidirectional"))
    )
    (net (code "75") (name "unconnected-(U$2-PadP$9)") (class "Default")
      (node (ref "U$2") (pin "P$9") (pinfunction "P$9_P$9") (pintype "bidirectional"))
    )
    (net (code "76") (name "unconnected-(U$2-PadP$10)") (class "Default")
      (node (ref "U$2") (pin "P$10") (pinfunction "P$10_P$10") (pintype "bidirectional"))
    )
    (net (code "77") (name "unconnected-(U$2-PadP$11)") (class "Default")
      (node (ref "U$2") (pin "P$11") (pinfunction "P$11_P$11") (pintype "bidirectional"))
    )
    (net (code "78") (name "unconnected-(U$2-PadP$12)") (class "Default")
      (node (ref "U$2") (pin "P$12") (pinfunction "P$12_P$12") (pintype "bidirectional"))
    )
    (net (code "79") (name "unconnected-(USBM-PadD+)") (class "Default")
      (node (ref "USBM") (pin "D+") (pinfunction "D+_D+") (pintype "bidirectional"))
    )
    (net (code "80") (name "unconnected-(USBM-PadD-)") (class "Default")
      (node (ref "USBM") (pin "D-") (pinfunction "D-_D-") (pintype "bidirectional"))
    )
  )
)
